# config-bank0.net
KiCad netlist of a schematic drawn in Altium Designer
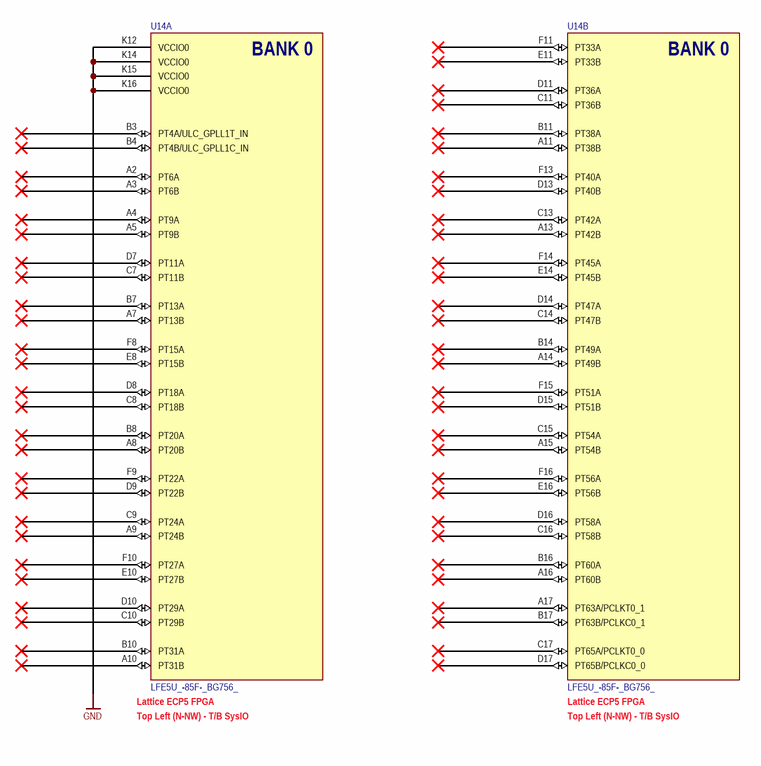
[diagram p0: config-bank0.SchDoc]

(export (version "E")
  (design (tool "Eeschema 10.0.6"))
  (components
    (comp (ref "U14")
      (value "LFE5U_-85F-_BG756_")
      (footprint "lattice:caBGA756")
      (description "ECP5 FPGA, 85k LUT, 756-caBGA")
      (fields (field (name "MANUFACTURER") "Lattice Semiconductor"))
      (libsource (lib "lattice") (part "LFE5U_-85F-_BG756_"))
    )
  )
  (nets
    (net (code "1") (name "GND") (class "Default")
      (node (ref "U14") (pin "K12") (pinfunction "VCCIO0_K12") (pintype "power_in"))
      (node (ref "U14") (pin "K14") (pinfunction "VCCIO0_K14") (pintype "power_in"))
      (node (ref "U14") (pin "K15") (pinfunction "VCCIO0_K15") (pintype "power_in"))
      (node (ref "U14") (pin "K16") (pinfunction "VCCIO0_K16") (pintype "power_in"))
    )
    (net (code "2") (name "unconnected-(U14A-PT4A{slash}ULC_GPLL1T_IN-PadB3)") (class "Default")
      (node (ref "U14") (pin "B3") (pinfunction "PT4A/ULC_GPLL1T_IN_B3") (pintype "bidirectional+no_connect"))
    )
    (net (code "3") (name "unconnected-(U14A-PT4B{slash}ULC_GPLL1C_IN-PadB4)") (class "Default")
      (node (ref "U14") (pin "B4") (pinfunction "PT4B/ULC_GPLL1C_IN_B4") (pintype "bidirectional+no_connect"))
    )
    (net (code "4") (name "unconnected-(U14A-PT6A-PadA2)") (class "Default")
      (node (ref "U14") (pin "A2") (pinfunction "PT6A_A2") (pintype "bidirectional+no_connect"))
    )
    (net (code "5") (name "unconnected-(U14A-PT6B-PadA3)") (class "Default")
      (node (ref "U14") (pin "A3") (pinfunction "PT6B_A3") (pintype "bidirectional+no_connect"))
    )
    (net (code "6") (name "unconnected-(U14A-PT9A-PadA4)") (class "Default")
      (node (ref "U14") (pin "A4") (pinfunction "PT9A_A4") (pintype "bidirectional+no_connect"))
    )
    (net (code "7") (name "unconnected-(U14A-PT9B-PadA5)") (class "Default")
      (node (ref "U14") (pin "A5") (pinfunction "PT9B_A5") (pintype "bidirectional+no_connect"))
    )
    (net (code "8") (name "unconnected-(U14A-PT11A-PadD7)") (class "Default")
      (node (ref "U14") (pin "D7") (pinfunction "PT11A_D7") (pintype "bidirectional+no_connect"))
    )
    (net (code "9") (name "unconnected-(U14A-PT11B-PadC7)") (class "Default")
      (node (ref "U14") (pin "C7") (pinfunction "PT11B_C7") (pintype "bidirectional+no_connect"))
    )
    (net (code "10") (name "unconnected-(U14A-PT13A-PadB7)") (class "Default")
      (node (ref "U14") (pin "B7") (pinfunction "PT13A_B7") (pintype "bidirectional+no_connect"))
    )
    (net (code "11") (name "unconnected-(U14A-PT13B-PadA7)") (class "Default")
      (node (ref "U14") (pin "A7") (pinfunction "PT13B_A7") (pintype "bidirectional+no_connect"))
    )
    (net (code "12") (name "unconnected-(U14A-PT15A-PadF8)") (class "Default")
      (node (ref "U14") (pin "F8") (pinfunction "PT15A_F8") (pintype "bidirectional+no_connect"))
    )
    (net (code "13") (name "unconnected-(U14A-PT15B-PadE8)") (class "Default")
      (node (ref "U14") (pin "E8") (pinfunction "PT15B_E8") (pintype "bidirectional+no_connect"))
    )
    (net (code "14") (name "unconnected-(U14A-PT18A-PadD8)") (class "Default")
      (node (ref "U14") (pin "D8") (pinfunction "PT18A_D8") (pintype "bidirectional+no_connect"))
    )
    (net (code "15") (name "unconnected-(U14A-PT18B-PadC8)") (class "Default")
      (node (ref "U14") (pin "C8") (pinfunction "PT18B_C8") (pintype "bidirectional+no_connect"))
    )
    (net (code "16") (name "unconnected-(U14A-PT20A-PadB8)") (class "Default")
      (node (ref "U14") (pin "B8") (pinfunction "PT20A_B8") (pintype "bidirectional+no_connect"))
    )
    (net (code "17") (name "unconnected-(U14A-PT20B-PadA8)") (class "Default")
      (node (ref "U14") (pin "A8") (pinfunction "PT20B_A8") (pintype "bidirectional+no_connect"))
    )
    (net (code "18") (name "unconnected-(U14A-PT22A-PadF9)") (class "Default")
      (node (ref "U14") (pin "F9") (pinfunction "PT22A_F9") (pintype "bidirectional+no_connect"))
    )
    (net (code "19") (name "unconnected-(U14A-PT22B-PadD9)") (class "Default")
      (node (ref "U14") (pin "D9") (pinfunction "PT22B_D9") (pintype "bidirectional+no_connect"))
    )
    (net (code "20") (name "unconnected-(U14A-PT24A-PadC9)") (class "Default")
      (node (ref "U14") (pin "C9") (pinfunction "PT24A_C9") (pintype "bidirectional+no_connect"))
    )
    (net (code "21") (name "unconnected-(U14A-PT24B-PadA9)") (class "Default")
      (node (ref "U14") (pin "A9") (pinfunction "PT24B_A9") (pintype "bidirectional+no_connect"))
    )
    (net (code "22") (name "unconnected-(U14A-PT27A-PadF10)") (class "Default")
      (node (ref "U14") (pin "F10") (pinfunction "PT27A_F10") (pintype "bidirectional+no_connect"))
    )
    (net (code "23") (name "unconnected-(U14A-PT27B-PadE10)") (class "Default")
      (node (ref "U14") (pin "E10") (pinfunction "PT27B_E10") (pintype "bidirectional+no_connect"))
    )
    (net (code "24") (name "unconnected-(U14A-PT29A-PadD10)") (class "Default")
      (node (ref "U14") (pin "D10") (pinfunction "PT29A_D10") (pintype "bidirectional+no_connect"))
    )
    (net (code "25") (name "unconnected-(U14A-PT29B-PadC10)") (class "Default")
      (node (ref "U14") (pin "C10") (pinfunction "PT29B_C10") (pintype "bidirectional+no_connect"))
    )
    (net (code "26") (name "unconnected-(U14A-PT31A-PadB10)") (class "Default")
      (node (ref "U14") (pin "B10") (pinfunction "PT31A_B10") (pintype "bidirectional+no_connect"))
    )
    (net (code "27") (name "unconnected-(U14A-PT31B-PadA10)") (class "Default")
      (node (ref "U14") (pin "A10") (pinfunction "PT31B_A10") (pintype "bidirectional+no_connect"))
    )
    (net (code "28") (name "unconnected-(U14B-PT33A-PadF11)") (class "Default")
      (node (ref "U14") (pin "F11") (pinfunction "PT33A_F11") (pintype "bidirectional+no_connect"))
    )
    (net (code "29") (name "unconnected-(U14B-PT33B-PadE11)") (class "Default")
      (node (ref "U14") (pin "E11") (pinfunction "PT33B_E11") (pintype "bidirectional+no_connect"))
    )
    (net (code "30") (name "unconnected-(U14B-PT36A-PadD11)") (class "Default")
      (node (ref "U14") (pin "D11") (pinfunction "PT36A_D11") (pintype "bidirectional+no_connect"))
    )
    (net (code "31") (name "unconnected-(U14B-PT36B-PadC11)") (class "Default")
      (node (ref "U14") (pin "C11") (pinfunction "PT36B_C11") (pintype "bidirectional+no_connect"))
    )
    (net (code "32") (name "unconnected-(U14B-PT38A-PadB11)") (class "Default")
      (node (ref "U14") (pin "B11") (pinfunction "PT38A_B11") (pintype "bidirectional+no_connect"))
    )
    (net (code "33") (name "unconnected-(U14B-PT38B-PadA11)") (class "Default")
      (node (ref "U14") (pin "A11") (pinfunction "PT38B_A11") (pintype "bidirectional+no_connect"))
    )
    (net (code "34") (name "unconnected-(U14B-PT40A-PadF13)") (class "Default")
      (node (ref "U14") (pin "F13") (pinfunction "PT40A_F13") (pintype "bidirectional+no_connect"))
    )
    (net (code "35") (name "unconnected-(U14B-PT40B-PadD13)") (class "Default")
      (node (ref "U14") (pin "D13") (pinfunction "PT40B_D13") (pintype "bidirectional+no_connect"))
    )
    (net (code "36") (name "unconnected-(U14B-PT42A-PadC13)") (class "Default")
      (node (ref "U14") (pin "C13") (pinfunction "PT42A_C13") (pintype "bidirectional+no_connect"))
    )
    (net (code "37") (name "unconnected-(U14B-PT42B-PadA13)") (class "Default")
      (node (ref "U14") (pin "A13") (pinfunction "PT42B_A13") (pintype "bidirectional+no_connect"))
    )
    (net (code "38") (name "unconnected-(U14B-PT45A-PadF14)") (class "Default")
      (node (ref "U14") (pin "F14") (pinfunction "PT45A_F14") (pintype "bidirectional+no_connect"))
    )
    (net (code "39") (name "unconnected-(U14B-PT45B-PadE14)") (class "Default")
      (node (ref "U14") (pin "E14") (pinfunction "PT45B_E14") (pintype "bidirectional+no_connect"))
    )
    (net (code "40") (name "unconnected-(U14B-PT47A-PadD14)") (class "Default")
      (node (ref "U14") (pin "D14") (pinfunction "PT47A_D14") (pintype "bidirectional+no_connect"))
    )
    (net (code "41") (name "unconnected-(U14B-PT47B-PadC14)") (class "Default")
      (node (ref "U14") (pin "C14") (pinfunction "PT47B_C14") (pintype "bidirectional+no_connect"))
    )
    (net (code "42") (name "unconnected-(U14B-PT49A-PadB14)") (class "Default")
      (node (ref "U14") (pin "B14") (pinfunction "PT49A_B14") (pintype "bidirectional+no_connect"))
    )
    (net (code "43") (name "unconnected-(U14B-PT49B-PadA14)") (class "Default")
      (node (ref "U14") (pin "A14") (pinfunction "PT49B_A14") (pintype "bidirectional+no_connect"))
    )
    (net (code "44") (name "unconnected-(U14B-PT51A-PadF15)") (class "Default")
      (node (ref "U14") (pin "F15") (pinfunction "PT51A_F15") (pintype "bidirectional+no_connect"))
    )
    (net (code "45") (name "unconnected-(U14B-PT51B-PadD15)") (class "Default")
      (node (ref "U14") (pin "D15") (pinfunction "PT51B_D15") (pintype "bidirectional+no_connect"))
    )
    (net (code "46") (name "unconnected-(U14B-PT54A-PadC15)") (class "Default")
      (node (ref "U14") (pin "C15") (pinfunction "PT54A_C15") (pintype "bidirectional+no_connect"))
    )
    (net (code "47") (name "unconnected-(U14B-PT54B-PadA15)") (class "Default")
      (node (ref "U14") (pin "A15") (pinfunction "PT54B_A15") (pintype "bidirectional+no_connect"))
    )
    (net (code "48") (name "unconnected-(U14B-PT56A-PadF16)") (class "Default")
      (node (ref "U14") (pin "F16") (pinfunction "PT56A_F16") (pintype "bidirectional+no_connect"))
    )
    (net (code "49") (name "unconnected-(U14B-PT56B-PadE16)") (class "Default")
      (node (ref "U14") (pin "E16") (pinfunction "PT56B_E16") (pintype "bidirectional+no_connect"))
    )
    (net (code "50") (name "unconnected-(U14B-PT58A-PadD16)") (class "Default")
      (node (ref "U14") (pin "D16") (pinfunction "PT58A_D16") (pintype "bidirectional+no_connect"))
    )
    (net (code "51") (name "unconnected-(U14B-PT58B-PadC16)") (class "Default")
      (node (ref "U14") (pin "C16") (pinfunction "PT58B_C16") (pintype "bidirectional+no_connect"))
    )
    (net (code "52") (name "unconnected-(U14B-PT60A-PadB16)") (class "Default")
      (node (ref "U14") (pin "B16") (pinfunction "PT60A_B16") (pintype "bidirectional+no_connect"))
    )
    (net (code "53") (name "unconnected-(U14B-PT60B-PadA16)") (class "Default")
      (node (ref "U14") (pin "A16") (pinfunction "PT60B_A16") (pintype "bidirectional+no_connect"))
    )
    (net (code "54") (name "unconnected-(U14B-PT63A{slash}PCLKT0_1-PadA17)") (class "Default")
      (node (ref "U14") (pin "A17") (pinfunction "PT63A/PCLKT0_1_A17") (pintype "bidirectional+no_connect"))
    )
    (net (code "55") (name "unconnected-(U14B-PT63B{slash}PCLKC0_1-PadB17)") (class "Default")
      (node (ref "U14") (pin "B17") (pinfunction "PT63B/PCLKC0_1_B17") (pintype "bidirectional+no_connect"))
    )
    (net (code "56") (name "unconnected-(U14B-PT65A{slash}PCLKT0_0-PadC17)") (class "Default")
      (node (ref "U14") (pin "C17") (pinfunction "PT65A/PCLKT0_0_C17") (pintype "bidirectional+no_connect"))
    )
    (net (code "57") (name "unconnected-(U14B-PT65B{slash}PCLKC0_0-PadD17)") (class "Default")
      (node (ref "U14") (pin "D17") (pinfunction "PT65B/PCLKC0_0_D17") (pintype "bidirectional+no_connect"))
    )
  )
)
